# ecu1_telemetria.net
KiCad netlist of a schematic drawn in EAGLE
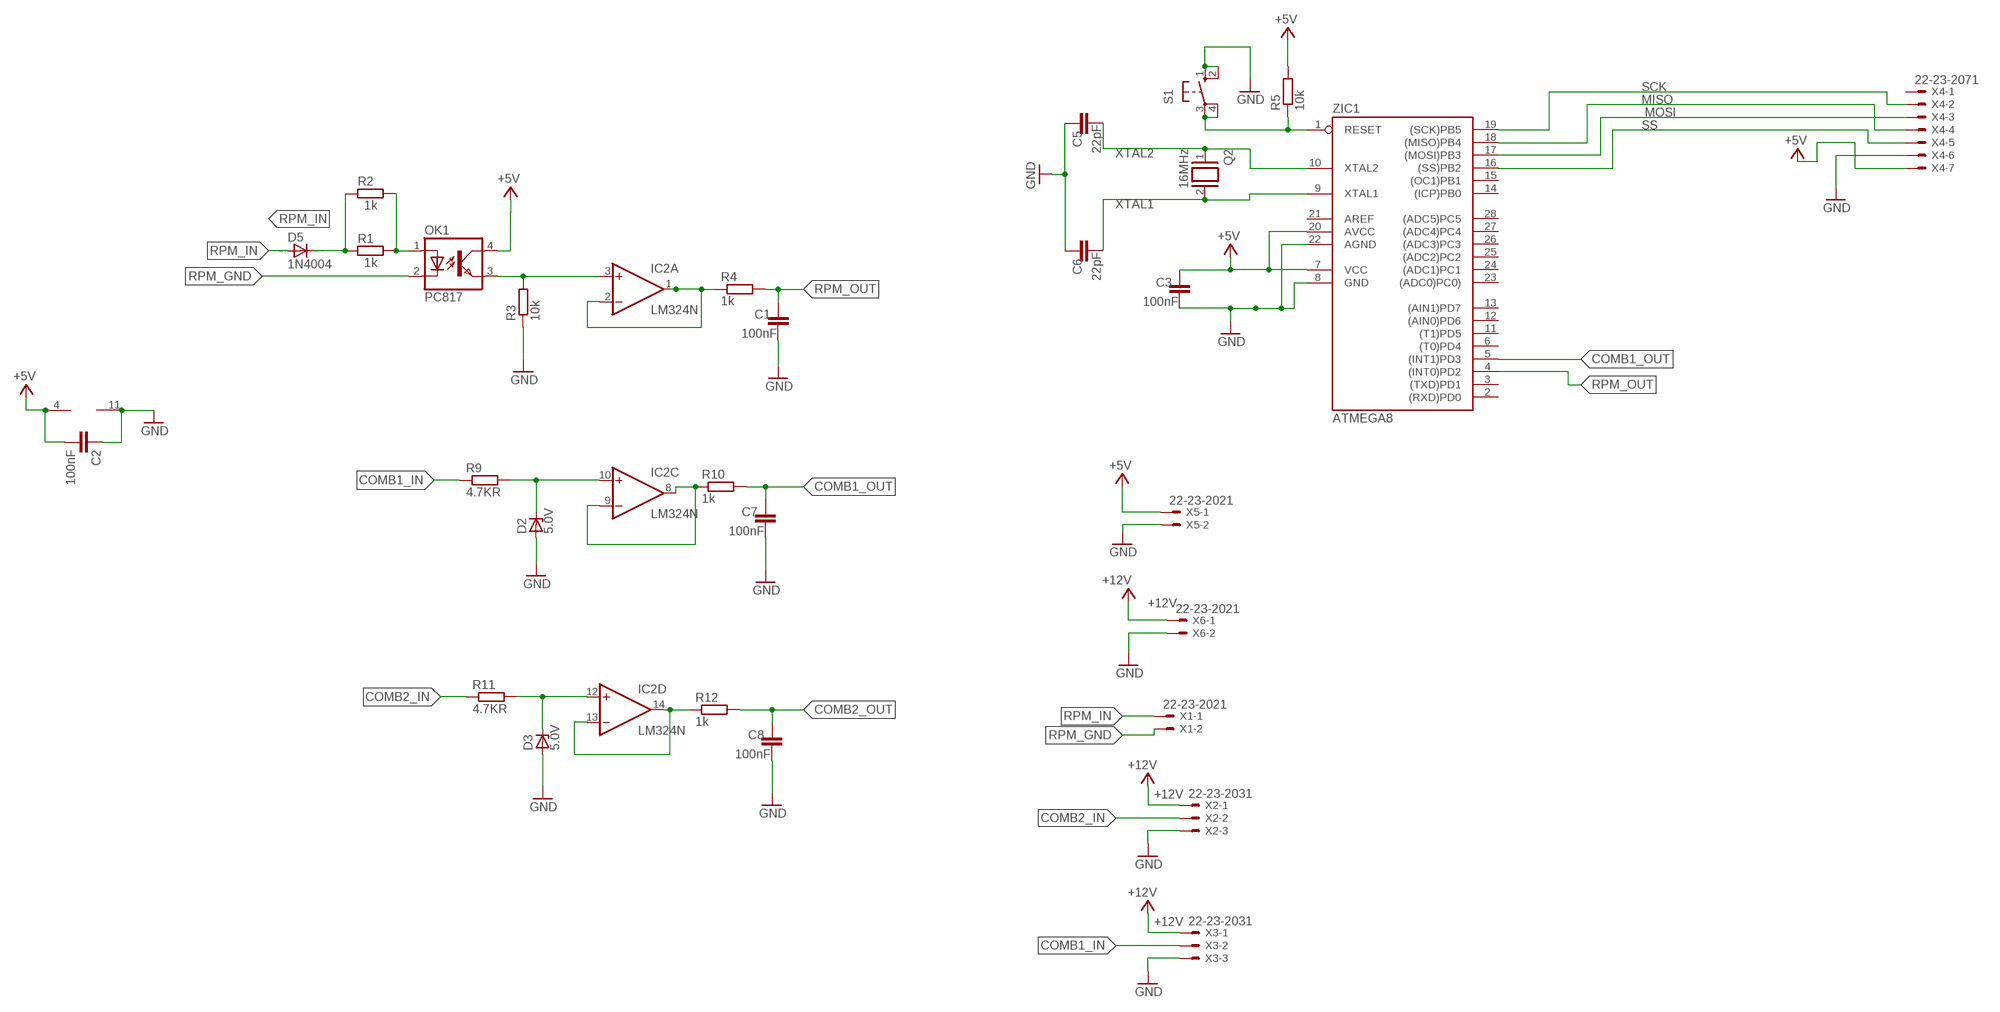
[diagram p0: schematic, sheet 1]

(export (version "E")
  (design (tool "Eeschema 10.0.6"))
  (components
    (comp (ref "C1")
      (value "100nF")
      (footprint "eagle-import:C5B2.5")
      (libsource (lib "eagle-import") (part "C5/2.5"))
    )
    (comp (ref "C2")
      (value "100nF")
      (footprint "eagle-import:C2.5-3")
      (libsource (lib "eagle-import") (part "C2,5-3"))
    )
    (comp (ref "C3")
      (value "100nF")
      (footprint "eagle-import:C5B2.5")
      (libsource (lib "eagle-import") (part "C5/2.5"))
    )
    (comp (ref "C5")
      (value "22pF")
      (footprint "eagle-import:C5B2.5")
      (libsource (lib "eagle-import") (part "C5/2.5"))
    )
    (comp (ref "C6")
      (value "22pF")
      (footprint "eagle-import:C5B2.5")
      (libsource (lib "eagle-import") (part "C5/2.5"))
    )
    (comp (ref "C7")
      (value "100nF")
      (footprint "eagle-import:C5B2.5")
      (libsource (lib "eagle-import") (part "C5/2.5"))
    )
    (comp (ref "C8")
      (value "100nF")
      (footprint "eagle-import:C5B2.5")
      (libsource (lib "eagle-import") (part "C5/2.5"))
    )
    (comp (ref "D2")
      (value "5.0V")
      (footprint "eagle-import:DO34Z7")
      (libsource (lib "eagle-import") (part "ZENER-DIODEDO34-7"))
    )
    (comp (ref "D3")
      (value "5.0V")
      (footprint "eagle-import:DO34Z7")
      (libsource (lib "eagle-import") (part "ZENER-DIODEDO34-7"))
    )
    (comp (ref "D5")
      (value "1N4004")
      (footprint "eagle-import:DO41-10")
      (libsource (lib "eagle-import") (part "1N4004"))
    )
    (comp (ref "IC2")
      (value "LM324N")
      (footprint "eagle-import:DIL14")
      (libsource (lib "eagle-import") (part "LM324N"))
    )
    (comp (ref "OK1")
      (value "PC817")
      (footprint "eagle-import:DIL04")
      (fields (field (name "MPN") "PC817X4J000F"))
      (libsource (lib "eagle-import") (part "PC817"))
    )
    (comp (ref "Q2")
      (value "16MHz")
      (footprint "eagle-import:QS")
      (libsource (lib "eagle-import") (part "XTAL/S"))
    )
    (comp (ref "R1")
      (value "1k")
      (footprint "eagle-import:0207_7")
      (libsource (lib "eagle-import") (part "R-EU_0207/7"))
    )
    (comp (ref "R2")
      (value "1k")
      (footprint "eagle-import:0207_7")
      (libsource (lib "eagle-import") (part "R-EU_0207/7"))
    )
    (comp (ref "R3")
      (value "10k")
      (footprint "eagle-import:0207_7")
      (libsource (lib "eagle-import") (part "R-EU_0207/7"))
    )
    (comp (ref "R4")
      (value "1k")
      (footprint "eagle-import:0207_7")
      (libsource (lib "eagle-import") (part "R-EU_0207/7"))
    )
    (comp (ref "R5")
      (value "10k")
      (footprint "eagle-import:0207_7")
      (libsource (lib "eagle-import") (part "R-EU_0207/7"))
    )
    (comp (ref "R9")
      (value "4.7KR")
      (footprint "eagle-import:0207_7")
      (libsource (lib "eagle-import") (part "R-EU_0207/7"))
    )
    (comp (ref "R10")
      (value "1k")
      (footprint "eagle-import:0207_7")
      (libsource (lib "eagle-import") (part "R-EU_0207/7"))
    )
    (comp (ref "R11")
      (value "4.7KR")
      (footprint "eagle-import:0207_7")
      (libsource (lib "eagle-import") (part "R-EU_0207/7"))
    )
    (comp (ref "R12")
      (value "1k")
      (footprint "eagle-import:0207_7")
      (libsource (lib "eagle-import") (part "R-EU_0207/7"))
    )
    (comp (ref "S1")
      (value "10-XX")
      (footprint "eagle-import:B3F-10XX")
      (fields (field (name "MPN") "B3F-1000"))
      (libsource (lib "eagle-import") (part "10-XX"))
    )
    (comp (ref "X1")
      (value "22-23-2021")
      (footprint "eagle-import:22-23-2021")
      (fields (field (name "MF") "MOLEX"))
      (libsource (lib "eagle-import") (part "22-23-2021"))
    )
    (comp (ref "X2")
      (value "22-23-2031")
      (footprint "eagle-import:22-23-2031")
      (fields (field (name "MF") "MOLEX"))
      (libsource (lib "eagle-import") (part "22-23-2031"))
    )
    (comp (ref "X3")
      (value "22-23-2031")
      (footprint "eagle-import:22-23-2031")
      (fields (field (name "MF") "MOLEX"))
      (libsource (lib "eagle-import") (part "22-23-2031"))
    )
    (comp (ref "X4")
      (value "22-23-2071")
      (footprint "eagle-import:22-23-2071")
      (fields (field (name "MF") "MOLEX"))
      (libsource (lib "eagle-import") (part "22-23-2071"))
    )
    (comp (ref "X5")
      (value "22-23-2021")
      (footprint "eagle-import:22-23-2021")
      (fields (field (name "MF") "MOLEX"))
      (libsource (lib "eagle-import") (part "22-23-2021"))
    )
    (comp (ref "X6")
      (value "22-23-2021")
      (footprint "eagle-import:22-23-2021")
      (fields (field (name "MF") "MOLEX"))
      (libsource (lib "eagle-import") (part "22-23-2021"))
    )
    (comp (ref "ZIC1")
      (value "ATMEGA8")
      (footprint "eagle-import:DIL28-3")
      (libsource (lib "eagle-import") (part "AT90S4433P"))
    )
  )
  (nets
    (net (code "1") (name "+5V") (class "Default")
      (node (ref "C2") (pin "2") (pinfunction "2_2") (pintype "passive"))
      (node (ref "C3") (pin "2") (pinfunction "2_2") (pintype "passive"))
      (node (ref "IC2") (pin "4") (pinfunction "V+_4") (pintype "power_in"))
      (node (ref "OK1") (pin "4") (pinfunction "COL_4") (pintype "passive"))
      (node (ref "R5") (pin "2") (pinfunction "2_2") (pintype "passive"))
      (node (ref "X4") (pin "7") (pinfunction "S_7") (pintype "passive"))
      (node (ref "X5") (pin "1") (pinfunction "S_1") (pintype "passive"))
      (node (ref "ZIC1") (pin "20") (pinfunction "AVCC_20") (pintype "power_in"))
      (node (ref "ZIC1") (pin "7") (pinfunction "VCC_7") (pintype "power_in"))
    )
    (net (code "2") (name "+12V") (class "Default")
      (node (ref "X2") (pin "1") (pinfunction "S_1") (pintype "passive"))
      (node (ref "X3") (pin "1") (pinfunction "S_1") (pintype "passive"))
      (node (ref "X6") (pin "1") (pinfunction "S_1") (pintype "passive"))
    )
    (net (code "3") (name "/MISO") (class "Default")
      (node (ref "X4") (pin "4") (pinfunction "S_4") (pintype "passive"))
      (node (ref "ZIC1") (pin "18") (pinfunction "(MISO)PB4_18") (pintype "bidirectional"))
    )
    (net (code "4") (name "/MOSI") (class "Default")
      (node (ref "X4") (pin "3") (pinfunction "S_3") (pintype "passive"))
      (node (ref "ZIC1") (pin "17") (pinfunction "(MOSI)PB3_17") (pintype "bidirectional"))
    )
    (net (code "5") (name "/SCK") (class "Default")
      (node (ref "X4") (pin "2") (pinfunction "S_2") (pintype "passive"))
      (node (ref "ZIC1") (pin "19") (pinfunction "(SCK)PB5_19") (pintype "bidirectional"))
    )
    (net (code "6") (name "/SS") (class "Default")
      (node (ref "X4") (pin "5") (pinfunction "S_5") (pintype "passive"))
      (node (ref "ZIC1") (pin "16") (pinfunction "(SS)PB2_16") (pintype "bidirectional"))
    )
    (net (code "7") (name "/XTAL1") (class "Default")
      (node (ref "C6") (pin "1") (pinfunction "1_1") (pintype "passive"))
      (node (ref "Q2") (pin "2") (pinfunction "2_2") (pintype "passive"))
      (node (ref "ZIC1") (pin "9") (pinfunction "XTAL1_9") (pintype "bidirectional"))
    )
    (net (code "8") (name "/XTAL2") (class "Default")
      (node (ref "C5") (pin "1") (pinfunction "1_1") (pintype "passive"))
      (node (ref "Q2") (pin "1") (pinfunction "1_1") (pintype "passive"))
      (node (ref "ZIC1") (pin "10") (pinfunction "XTAL2_10") (pintype "bidirectional"))
    )
    (net (code "9") (name "COMB1_IN") (class "Default")
      (node (ref "R9") (pin "1") (pinfunction "1_1") (pintype "passive"))
      (node (ref "X3") (pin "2") (pinfunction "S_2") (pintype "passive"))
    )
    (net (code "10") (name "COMB1_OUT") (class "Default")
      (node (ref "C7") (pin "2") (pinfunction "2_2") (pintype "passive"))
      (node (ref "R10") (pin "2") (pinfunction "2_2") (pintype "passive"))
      (node (ref "ZIC1") (pin "5") (pinfunction "(INT1)PD3_5") (pintype "bidirectional"))
    )
    (net (code "11") (name "COMB2_IN") (class "Default")
      (node (ref "R11") (pin "1") (pinfunction "1_1") (pintype "passive"))
      (node (ref "X2") (pin "2") (pinfunction "S_2") (pintype "passive"))
    )
    (net (code "12") (name "COMB2_OUT") (class "Default")
      (node (ref "C8") (pin "2") (pinfunction "2_2") (pintype "passive"))
      (node (ref "R12") (pin "2") (pinfunction "2_2") (pintype "passive"))
    )
    (net (code "13") (name "GND") (class "Default")
      (node (ref "C1") (pin "1") (pinfunction "1_1") (pintype "passive"))
      (node (ref "C2") (pin "1") (pinfunction "1_1") (pintype "passive"))
      (node (ref "C3") (pin "1") (pinfunction "1_1") (pintype "passive"))
      (node (ref "C5") (pin "2") (pinfunction "2_2") (pintype "passive"))
      (node (ref "C6") (pin "2") (pinfunction "2_2") (pintype "passive"))
      (node (ref "C7") (pin "1") (pinfunction "1_1") (pintype "passive"))
      (node (ref "C8") (pin "1") (pinfunction "1_1") (pintype "passive"))
      (node (ref "D2") (pin "A") (pinfunction "A_A") (pintype "passive"))
      (node (ref "D3") (pin "A") (pinfunction "A_A") (pintype "passive"))
      (node (ref "IC2") (pin "11") (pinfunction "V-_11") (pintype "power_in"))
      (node (ref "R3") (pin "1") (pinfunction "1_1") (pintype "passive"))
      (node (ref "S1") (pin "1") (pinfunction "S_1") (pintype "passive"))
      (node (ref "S1") (pin "2") (pinfunction "S1_2") (pintype "passive"))
      (node (ref "X2") (pin "3") (pinfunction "S_3") (pintype "passive"))
      (node (ref "X3") (pin "3") (pinfunction "S_3") (pintype "passive"))
      (node (ref "X4") (pin "6") (pinfunction "S_6") (pintype "passive"))
      (node (ref "X5") (pin "2") (pinfunction "S_2") (pintype "passive"))
      (node (ref "X6") (pin "2") (pinfunction "S_2") (pintype "passive"))
      (node (ref "ZIC1") (pin "22") (pinfunction "AGND_22") (pintype "power_in"))
      (node (ref "ZIC1") (pin "8") (pinfunction "GND_8") (pintype "power_in"))
    )
    (net (code "14") (name "Net-(D5-PadC)") (class "Default")
      (node (ref "D5") (pin "C") (pinfunction "C_C") (pintype "passive"))
      (node (ref "R1") (pin "1") (pinfunction "1_1") (pintype "passive"))
      (node (ref "R2") (pin "1") (pinfunction "1_1") (pintype "passive"))
    )
    (net (code "15") (name "Net-(IC2A-+IN)") (class "Default")
      (node (ref "IC2") (pin "3") (pinfunction "+IN_3") (pintype "input"))
      (node (ref "OK1") (pin "3") (pinfunction "EMIT_3") (pintype "passive"))
      (node (ref "R3") (pin "2") (pinfunction "2_2") (pintype "passive"))
    )
    (net (code "16") (name "Net-(IC2A--IN)") (class "Default")
      (node (ref "IC2") (pin "1") (pinfunction "OUT_1") (pintype "output"))
      (node (ref "IC2") (pin "2") (pinfunction "-IN_2") (pintype "input"))
      (node (ref "R4") (pin "1") (pinfunction "1_1") (pintype "passive"))
    )
    (net (code "17") (name "Net-(IC2C-+IN)") (class "Default")
      (node (ref "D2") (pin "C") (pinfunction "C_C") (pintype "passive"))
      (node (ref "IC2") (pin "10") (pinfunction "+IN_10") (pintype "input"))
      (node (ref "R9") (pin "2") (pinfunction "2_2") (pintype "passive"))
    )
    (net (code "18") (name "Net-(IC2C--IN)") (class "Default")
      (node (ref "IC2") (pin "8") (pinfunction "OUT_8") (pintype "output"))
      (node (ref "IC2") (pin "9") (pinfunction "-IN_9") (pintype "input"))
      (node (ref "R10") (pin "1") (pinfunction "1_1") (pintype "passive"))
    )
    (net (code "19") (name "Net-(IC2D-+IN)") (class "Default")
      (node (ref "D3") (pin "C") (pinfunction "C_C") (pintype "passive"))
      (node (ref "IC2") (pin "12") (pinfunction "+IN_12") (pintype "input"))
      (node (ref "R11") (pin "2") (pinfunction "2_2") (pintype "passive"))
    )
    (net (code "20") (name "Net-(IC2D--IN)") (class "Default")
      (node (ref "IC2") (pin "13") (pinfunction "-IN_13") (pintype "input"))
      (node (ref "IC2") (pin "14") (pinfunction "OUT_14") (pintype "output"))
      (node (ref "R12") (pin "1") (pinfunction "1_1") (pintype "passive"))
    )
    (net (code "21") (name "Net-(OK1-A)") (class "Default")
      (node (ref "OK1") (pin "1") (pinfunction "A_1") (pintype "passive"))
      (node (ref "R1") (pin "2") (pinfunction "2_2") (pintype "passive"))
      (node (ref "R2") (pin "2") (pinfunction "2_2") (pintype "passive"))
    )
    (net (code "22") (name "Net-(S1-P)") (class "Default")
      (node (ref "R5") (pin "1") (pinfunction "1_1") (pintype "passive"))
      (node (ref "S1") (pin "3") (pinfunction "P_3") (pintype "passive"))
      (node (ref "S1") (pin "4") (pinfunction "P1_4") (pintype "passive"))
      (node (ref "ZIC1") (pin "1") (pinfunction "RESET_1") (pintype "input"))
    )
    (net (code "23") (name "RPM_GND") (class "Default")
      (node (ref "OK1") (pin "2") (pinfunction "C_2") (pintype "passive"))
      (node (ref "X1") (pin "2") (pinfunction "S_2") (pintype "passive"))
    )
    (net (code "24") (name "RPM_IN") (class "Default")
      (node (ref "D5") (pin "A") (pinfunction "A_A") (pintype "passive"))
      (node (ref "X1") (pin "1") (pinfunction "S_1") (pintype "passive"))
    )
    (net (code "25") (name "RPM_OUT") (class "Default")
      (node (ref "C1") (pin "2") (pinfunction "2_2") (pintype "passive"))
      (node (ref "R4") (pin "2") (pinfunction "2_2") (pintype "passive"))
      (node (ref "ZIC1") (pin "4") (pinfunction "(INT0)PD2_4") (pintype "bidirectional"))
    )
    (net (code "26") (name "unconnected-(X4A-S-Pad1)") (class "Default")
      (node (ref "X4") (pin "1") (pinfunction "S_1") (pintype "passive"))
    )
    (net (code "27") (name "unconnected-(ZIC1-(ADC0)PC0)-Pad23)") (class "Default")
      (node (ref "ZIC1") (pin "23") (pinfunction "(ADC0)PC0)_23") (pintype "bidirectional"))
    )
    (net (code "28") (name "unconnected-(ZIC1-(ADC1)PC1-Pad24)") (class "Default")
      (node (ref "ZIC1") (pin "24") (pinfunction "(ADC1)PC1_24") (pintype "bidirectional"))
    )
    (net (code "29") (name "unconnected-(ZIC1-(ADC2)PC2-Pad25)") (class "Default")
      (node (ref "ZIC1") (pin "25") (pinfunction "(ADC2)PC2_25") (pintype "bidirectional"))
    )
    (net (code "30") (name "unconnected-(ZIC1-(ADC3)PC3-Pad26)") (class "Default")
      (node (ref "ZIC1") (pin "26") (pinfunction "(ADC3)PC3_26") (pintype "bidirectional"))
    )
    (net (code "31") (name "unconnected-(ZIC1-(ADC4)PC4-Pad27)") (class "Default")
      (node (ref "ZIC1") (pin "27") (pinfunction "(ADC4)PC4_27") (pintype "bidirectional"))
    )
    (net (code "32") (name "unconnected-(ZIC1-(ADC5)PC5-Pad28)") (class "Default")
      (node (ref "ZIC1") (pin "28") (pinfunction "(ADC5)PC5_28") (pintype "bidirectional"))
    )
    (net (code "33") (name "unconnected-(ZIC1-(AIN0)PD6-Pad12)") (class "Default")
      (node (ref "ZIC1") (pin "12") (pinfunction "(AIN0)PD6_12") (pintype "bidirectional"))
    )
    (net (code "34") (name "unconnected-(ZIC1-(AIN1)PD7-Pad13)") (class "Default")
      (node (ref "ZIC1") (pin "13") (pinfunction "(AIN1)PD7_13") (pintype "bidirectional"))
    )
    (net (code "35") (name "unconnected-(ZIC1-(ICP)PB0-Pad14)") (class "Default")
      (node (ref "ZIC1") (pin "14") (pinfunction "(ICP)PB0_14") (pintype "bidirectional"))
    )
    (net (code "36") (name "unconnected-(ZIC1-(OC1)PB1-Pad15)") (class "Default")
      (node (ref "ZIC1") (pin "15") (pinfunction "(OC1)PB1_15") (pintype "bidirectional"))
    )
    (net (code "37") (name "unconnected-(ZIC1-(RXD)PD0-Pad2)") (class "Default")
      (node (ref "ZIC1") (pin "2") (pinfunction "(RXD)PD0_2") (pintype "bidirectional"))
    )
    (net (code "38") (name "unconnected-(ZIC1-(T0)PD4-Pad6)") (class "Default")
      (node (ref "ZIC1") (pin "6") (pinfunction "(T0)PD4_6") (pintype "bidirectional"))
    )
    (net (code "39") (name "unconnected-(ZIC1-(T1)PD5-Pad11)") (class "Default")
      (node (ref "ZIC1") (pin "11") (pinfunction "(T1)PD5_11") (pintype "bidirectional"))
    )
    (net (code "40") (name "unconnected-(ZIC1-(TXD)PD1-Pad3)") (class "Default")
      (node (ref "ZIC1") (pin "3") (pinfunction "(TXD)PD1_3") (pintype "bidirectional"))
    )
    (net (code "41") (name "unconnected-(ZIC1-AREF-Pad21)") (class "Default")
      (node (ref "ZIC1") (pin "21") (pinfunction "AREF_21") (pintype "passive"))
    )
  )
)
